# BMS_rev2.net
KiCad netlist of a schematic drawn in Altium Designer
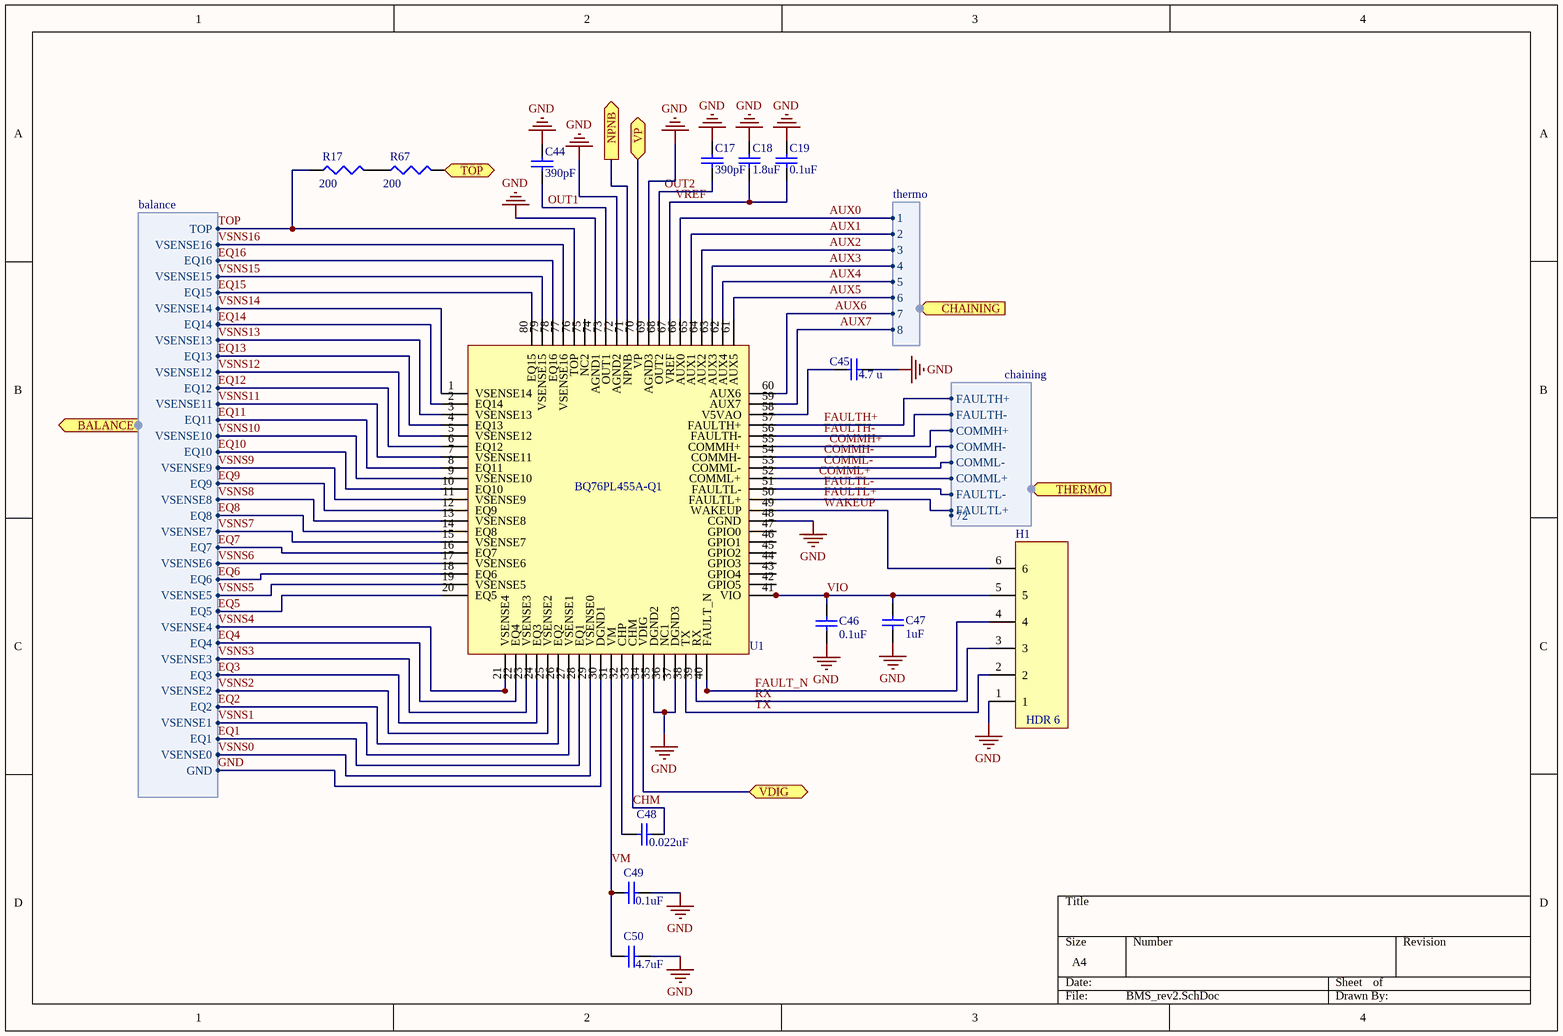
[diagram p0: BMS_rev2.SchDoc]

(export (version "E")
  (design (tool "Eeschema 10.0.6"))
  (components
    (comp (ref "C17")
      (value "390pF")
      (footprint "0805 CAP")
      (description "Capacitor (Semiconductor SIM Model)")
      (fields
        (field (name "MANUFACTURER") "Kyocera AVX")
        (field (name "MANUFACTURER PART NUMBER") "08055A391JAT2A")
        (field (name "PUBLISHER") "Altium Limited")
      )
      (libsource (lib "Miscellaneous Devices") (part "Cap Semi"))
    )
    (comp (ref "C18")
      (value "1.8uF")
      (footprint "1210 cap")
      (description "Capacitor (Semiconductor SIM Model)")
      (fields
        (field (name "MANUFACTURER") "KEMET")
        (field (name "MANUFACTURER PART NUMBER") "C1210C185K3RACTU")
        (field (name "PUBLISHER") "Altium Limited")
      )
      (libsource (lib "Miscellaneous Devices") (part "Cap Semi"))
    )
    (comp (ref "C19")
      (value "0.1uF")
      (footprint "0603 CAP")
      (description "Capacitor (Semiconductor SIM Model)")
      (fields
        (field (name "MANUFACTURER") "KEMET")
        (field (name "MANUFACTURER PART NUMBER") "C0603X104K3RACTU")
        (field (name "PUBLISHER") "Altium Limited")
      )
      (libsource (lib "Miscellaneous Devices") (part "Cap Semi"))
    )
    (comp (ref "C44")
      (value "390pF")
      (footprint "0805 CAP")
      (description "Capacitor (Semiconductor SIM Model)")
      (fields
        (field (name "MANUFACTURER") "Kyocera AVX")
        (field (name "MANUFACTURER PART NUMBER") "08055A391JAT2A")
        (field (name "PUBLISHER") "Altium Limited")
      )
      (libsource (lib "Miscellaneous Devices") (part "Cap Semi"))
    )
    (comp (ref "C45")
      (value "4.7 u")
      (footprint "0805 CAP")
      (description "Capacitor (Semiconductor SIM Model)")
      (fields
        (field (name "MANUFACTURER") "Murata")
        (field (name "MANUFACTURER PART NUMBER") "GRM21BR71C475KA73L")
        (field (name "PUBLISHER") "Altium Limited")
      )
      (libsource (lib "Miscellaneous Devices") (part "Cap Semi"))
    )
    (comp (ref "C46")
      (value "0.1uF")
      (footprint "0603 CAP")
      (description "Capacitor (Semiconductor SIM Model)")
      (fields
        (field (name "MANUFACTURER") "KEMET")
        (field (name "MANUFACTURER PART NUMBER") "C0603X104K3RACTU")
        (field (name "PUBLISHER") "Altium Limited")
      )
      (libsource (lib "Miscellaneous Devices") (part "Cap Semi"))
    )
    (comp (ref "C47")
      (value "1uF")
      (footprint "0603 CAP")
      (description "Capacitor (Semiconductor SIM Model)")
      (fields
        (field (name "MANUFACTURER") "TDK")
        (field (name "MANUFACTURER PART NUMBER") "C1608X7R1C105K080AC")
        (field (name "PUBLISHER") "Altium Limited")
      )
      (libsource (lib "Miscellaneous Devices") (part "Cap Semi"))
    )
    (comp (ref "C48")
      (value "0.022uF")
      (footprint "0603 CAP")
      (description "Capacitor (Semiconductor SIM Model)")
      (fields
        (field (name "MANUFACTURER") "TDK")
        (field (name "MANUFACTURER PART NUMBER") "C1608X7R1H223K080AA")
        (field (name "PUBLISHER") "Altium Limited")
      )
      (libsource (lib "Miscellaneous Devices") (part "Cap Semi"))
    )
    (comp (ref "C49")
      (value "0.1uF")
      (footprint "0603 CAP")
      (description "Capacitor (Semiconductor SIM Model)")
      (fields
        (field (name "MANUFACTURER") "KEMET")
        (field (name "MANUFACTURER PART NUMBER") "C0603X104K3RACTU")
        (field (name "PUBLISHER") "Altium Limited")
      )
      (libsource (lib "Miscellaneous Devices") (part "Cap Semi"))
    )
    (comp (ref "C50")
      (value "4.7uF")
      (footprint "0805 CAP")
      (description "Capacitor (Semiconductor SIM Model)")
      (fields
        (field (name "MANUFACTURER") "Murata")
        (field (name "MANUFACTURER PART NUMBER") "GRM21BR71C475KA73L")
        (field (name "PUBLISHER") "Altium Limited")
      )
      (libsource (lib "Miscellaneous Devices") (part "Cap Semi"))
    )
    (comp (ref "H1")
      (value "HDR 6")
      (footprint "SERIAL HDR")
      (fields (field (name "MANUFACTURER") "Molex") (field (name "MANUFACTURER PART NUMBER") "0022124062"))
      (libsource (lib "parts") (part "HDR 6"))
    )
    (comp (ref "R17")
      (value "200")
      (footprint "2512 RES")
      (description "Resistor")
      (fields
        (field (name "MANUFACTURER") "Vishay Dale")
        (field (name "MANUFACTURER PART NUMBER") "CRCW2512200RJNEG")
        (field (name "PUBLISHER") "Altium Limited")
      )
      (libsource (lib "Miscellaneous Devices") (part "Res3"))
    )
    (comp (ref "R67")
      (value "200")
      (footprint "2512 RES")
      (description "Resistor")
      (fields
        (field (name "MANUFACTURER") "Vishay Dale")
        (field (name "MANUFACTURER PART NUMBER") "CRCW2512200RJNEG")
        (field (name "PUBLISHER") "Altium Limited")
      )
      (libsource (lib "Miscellaneous Devices") (part "Res3"))
    )
    (comp (ref "U1")
      (value "BQ76PL455A-Q1")
      (footprint "BQ76PL455A-Q1")
      (fields
        (field (name "MANUFACTURER") "Texas Instruments")
        (field (name "MANUFACTURER PART NUMBER") "BQ76PL455ATPFCRQ1")
      )
      (libsource (lib "parts") (part "BQ76PL455A-Q1"))
    )
  )
  (nets
    (net (code "4") (name "/AUX0") (class "Default")
      (node (ref "U1") (pin "66") (pinfunction "AUX0_66") (pintype "passive"))
    )
    (net (code "5") (name "/AUX1") (class "Default")
      (node (ref "U1") (pin "65") (pinfunction "AUX1_65") (pintype "passive"))
    )
    (net (code "6") (name "/AUX2") (class "Default")
      (node (ref "U1") (pin "64") (pinfunction "AUX2_64") (pintype "passive"))
    )
    (net (code "7") (name "/AUX3") (class "Default")
      (node (ref "U1") (pin "63") (pinfunction "AUX3_63") (pintype "passive"))
    )
    (net (code "8") (name "/AUX4") (class "Default")
      (node (ref "U1") (pin "62") (pinfunction "AUX4_62") (pintype "passive"))
    )
    (net (code "9") (name "/AUX5") (class "Default")
      (node (ref "U1") (pin "61") (pinfunction "AUX5_61") (pintype "passive"))
    )
    (net (code "10") (name "/AUX6") (class "Default")
      (node (ref "U1") (pin "60") (pinfunction "AUX6_60") (pintype "passive"))
    )
    (net (code "11") (name "/AUX7") (class "Default")
      (node (ref "U1") (pin "59") (pinfunction "AUX7_59") (pintype "passive"))
    )
    (net (code "12") (name "/CHM") (class "Default")
      (node (ref "C48") (pin "2") (pinfunction "2_2") (pintype "passive"))
      (node (ref "U1") (pin "33") (pinfunction "CHM_33") (pintype "passive"))
    )
    (net (code "13") (name "/COMMH+") (class "Default")
      (node (ref "U1") (pin "55") (pinfunction "COMMH+_55") (pintype "passive"))
    )
    (net (code "14") (name "/COMMH-") (class "Default")
      (node (ref "U1") (pin "54") (pinfunction "COMMH-_54") (pintype "passive"))
    )
    (net (code "15") (name "/COMML+") (class "Default")
      (node (ref "U1") (pin "52") (pinfunction "COMML+_52") (pintype "passive"))
    )
    (net (code "16") (name "/COMML-") (class "Default")
      (node (ref "U1") (pin "53") (pinfunction "COMML-_53") (pintype "passive"))
    )
    (net (code "17") (name "/EQ1") (class "Default")
      (node (ref "U1") (pin "28") (pinfunction "EQ1_28") (pintype "passive"))
    )
    (net (code "18") (name "/EQ2") (class "Default")
      (node (ref "U1") (pin "26") (pinfunction "EQ2_26") (pintype "passive"))
    )
    (net (code "19") (name "/EQ3") (class "Default")
      (node (ref "U1") (pin "24") (pinfunction "EQ3_24") (pintype "passive"))
    )
    (net (code "20") (name "/EQ4") (class "Default")
      (node (ref "U1") (pin "22") (pinfunction "EQ4_22") (pintype "passive"))
    )
    (net (code "21") (name "/EQ5") (class "Default")
      (node (ref "U1") (pin "20") (pinfunction "EQ5_20") (pintype "passive"))
    )
    (net (code "22") (name "/EQ6") (class "Default")
      (node (ref "U1") (pin "18") (pinfunction "EQ6_18") (pintype "passive"))
    )
    (net (code "23") (name "/EQ7") (class "Default")
      (node (ref "U1") (pin "16") (pinfunction "EQ7_16") (pintype "passive"))
    )
    (net (code "24") (name "/EQ8") (class "Default")
      (node (ref "U1") (pin "14") (pinfunction "EQ8_14") (pintype "passive"))
    )
    (net (code "25") (name "/EQ9") (class "Default")
      (node (ref "U1") (pin "12") (pinfunction "EQ9_12") (pintype "passive"))
    )
    (net (code "26") (name "/EQ10") (class "Default")
      (node (ref "U1") (pin "10") (pinfunction "EQ10_10") (pintype "passive"))
    )
    (net (code "27") (name "/EQ11") (class "Default")
      (node (ref "U1") (pin "8") (pinfunction "EQ11_8") (pintype "passive"))
    )
    (net (code "28") (name "/EQ12") (class "Default")
      (node (ref "U1") (pin "6") (pinfunction "EQ12_6") (pintype "passive"))
    )
    (net (code "29") (name "/EQ13") (class "Default")
      (node (ref "U1") (pin "4") (pinfunction "EQ13_4") (pintype "passive"))
    )
    (net (code "30") (name "/EQ14") (class "Default")
      (node (ref "U1") (pin "2") (pinfunction "EQ14_2") (pintype "passive"))
    )
    (net (code "31") (name "/EQ15") (class "Default")
      (node (ref "U1") (pin "80") (pinfunction "EQ15_80") (pintype "passive"))
    )
    (net (code "32") (name "/EQ16") (class "Default")
      (node (ref "U1") (pin "78") (pinfunction "EQ16_78") (pintype "passive"))
    )
    (net (code "33") (name "/FAULTH+") (class "Default")
      (node (ref "U1") (pin "57") (pinfunction "FAULTH+_57") (pintype "passive"))
    )
    (net (code "34") (name "/FAULTH-") (class "Default")
      (node (ref "U1") (pin "56") (pinfunction "FAULTH-_56") (pintype "passive"))
    )
    (net (code "35") (name "/FAULTL+") (class "Default")
      (node (ref "U1") (pin "50") (pinfunction "FAULTL+_50") (pintype "passive"))
    )
    (net (code "36") (name "/FAULTL-") (class "Default")
      (node (ref "U1") (pin "51") (pinfunction "FAULTL-_51") (pintype "passive"))
    )
    (net (code "37") (name "/FAULT_N") (class "Default")
      (node (ref "H1") (pin "4") (pinfunction "4_4") (pintype "passive"))
      (node (ref "U1") (pin "40") (pinfunction "FAULT_N_40") (pintype "passive"))
    )
    (net (code "38") (name "/NPNB") (class "Default")
      (node (ref "U1") (pin "71") (pinfunction "NPNB_71") (pintype "passive"))
    )
    (net (code "39") (name "/OUT1") (class "Default")
      (node (ref "C44") (pin "2") (pinfunction "2_2") (pintype "passive"))
      (node (ref "U1") (pin "73") (pinfunction "OUT1_73") (pintype "passive"))
    )
    (net (code "40") (name "/OUT2") (class "Default")
      (node (ref "C17") (pin "2") (pinfunction "2_2") (pintype "passive"))
      (node (ref "U1") (pin "68") (pinfunction "OUT2_68") (pintype "passive"))
    )
    (net (code "41") (name "/RX") (class "Default")
      (node (ref "H1") (pin "3") (pinfunction "3_3") (pintype "passive"))
      (node (ref "U1") (pin "39") (pinfunction "RX_39") (pintype "passive"))
    )
    (net (code "42") (name "/TOP") (class "Default")
      (node (ref "R17") (pin "1") (pinfunction "1_1") (pintype "passive"))
      (node (ref "U1") (pin "76") (pinfunction "TOP_76") (pintype "passive"))
    )
    (net (code "43") (name "/TX") (class "Default")
      (node (ref "H1") (pin "2") (pinfunction "2_2") (pintype "passive"))
      (node (ref "U1") (pin "38") (pinfunction "TX_38") (pintype "passive"))
    )
    (net (code "44") (name "/VDIG") (class "Default")
      (node (ref "U1") (pin "34") (pinfunction "VDIG_34") (pintype "passive"))
    )
    (net (code "45") (name "/VIO") (class "Default")
      (node (ref "C46") (pin "2") (pinfunction "2_2") (pintype "passive"))
      (node (ref "C47") (pin "2") (pinfunction "2_2") (pintype "passive"))
      (node (ref "H1") (pin "5") (pinfunction "5_5") (pintype "passive"))
      (node (ref "U1") (pin "41") (pinfunction "VIO_41") (pintype "passive"))
    )
    (net (code "46") (name "/VM") (class "Default")
      (node (ref "C49") (pin "1") (pinfunction "1_1") (pintype "passive"))
      (node (ref "C50") (pin "1") (pinfunction "1_1") (pintype "passive"))
      (node (ref "U1") (pin "31") (pinfunction "VM_31") (pintype "passive"))
    )
    (net (code "47") (name "/VP") (class "Default")
      (node (ref "U1") (pin "70") (pinfunction "VP_70") (pintype "passive"))
    )
    (net (code "48") (name "/VREF") (class "Default")
      (node (ref "C18") (pin "2") (pinfunction "2_2") (pintype "passive"))
      (node (ref "C19") (pin "2") (pinfunction "2_2") (pintype "passive"))
      (node (ref "U1") (pin "67") (pinfunction "VREF_67") (pintype "passive"))
    )
    (net (code "49") (name "/VSNS0") (class "Default")
      (node (ref "U1") (pin "29") (pinfunction "VSENSE0_29") (pintype "passive"))
    )
    (net (code "50") (name "/VSNS1") (class "Default")
      (node (ref "U1") (pin "27") (pinfunction "VSENSE1_27") (pintype "passive"))
    )
    (net (code "51") (name "/VSNS2") (class "Default")
      (node (ref "U1") (pin "25") (pinfunction "VSENSE2_25") (pintype "passive"))
    )
    (net (code "52") (name "/VSNS3") (class "Default")
      (node (ref "U1") (pin "23") (pinfunction "VSENSE3_23") (pintype "passive"))
    )
    (net (code "53") (name "/VSNS4") (class "Default")
      (node (ref "U1") (pin "21") (pinfunction "VSENSE4_21") (pintype "passive"))
    )
    (net (code "54") (name "/VSNS5") (class "Default")
      (node (ref "U1") (pin "19") (pinfunction "VSENSE5_19") (pintype "passive"))
    )
    (net (code "55") (name "/VSNS6") (class "Default")
      (node (ref "U1") (pin "17") (pinfunction "VSENSE6_17") (pintype "passive"))
    )
    (net (code "56") (name "/VSNS7") (class "Default")
      (node (ref "U1") (pin "15") (pinfunction "VSENSE7_15") (pintype "passive"))
    )
    (net (code "57") (name "/VSNS8") (class "Default")
      (node (ref "U1") (pin "13") (pinfunction "VSENSE8_13") (pintype "passive"))
    )
    (net (code "58") (name "/VSNS9") (class "Default")
      (node (ref "U1") (pin "11") (pinfunction "VSENSE9_11") (pintype "passive"))
    )
    (net (code "59") (name "/VSNS10") (class "Default")
      (node (ref "U1") (pin "9") (pinfunction "VSENSE10_9") (pintype "passive"))
    )
    (net (code "60") (name "/VSNS11") (class "Default")
      (node (ref "U1") (pin "7") (pinfunction "VSENSE11_7") (pintype "passive"))
    )
    (net (code "61") (name "/VSNS12") (class "Default")
      (node (ref "U1") (pin "5") (pinfunction "VSENSE12_5") (pintype "passive"))
    )
    (net (code "62") (name "/VSNS13") (class "Default")
      (node (ref "U1") (pin "3") (pinfunction "VSENSE13_3") (pintype "passive"))
    )
    (net (code "63") (name "/VSNS14") (class "Default")
      (node (ref "U1") (pin "1") (pinfunction "VSENSE14_1") (pintype "passive"))
    )
    (net (code "64") (name "/VSNS15") (class "Default")
      (node (ref "U1") (pin "79") (pinfunction "VSENSE15_79") (pintype "passive"))
    )
    (net (code "65") (name "/VSNS16") (class "Default")
      (node (ref "U1") (pin "77") (pinfunction "VSENSE16_77") (pintype "passive"))
    )
    (net (code "66") (name "/WAKEUP") (class "Default")
      (node (ref "H1") (pin "6") (pinfunction "6_6") (pintype "passive"))
      (node (ref "U1") (pin "49") (pinfunction "WAKEUP_49") (pintype "passive"))
    )
    (net (code "70") (name "GND") (class "Default")
      (node (ref "C17") (pin "1") (pinfunction "1_1") (pintype "passive"))
      (node (ref "C18") (pin "1") (pinfunction "1_1") (pintype "passive"))
      (node (ref "C19") (pin "1") (pinfunction "1_1") (pintype "passive"))
      (node (ref "C44") (pin "1") (pinfunction "1_1") (pintype "passive"))
      (node (ref "C45") (pin "2") (pinfunction "2_2") (pintype "passive"))
      (node (ref "C46") (pin "1") (pinfunction "1_1") (pintype "passive"))
      (node (ref "C47") (pin "1") (pinfunction "1_1") (pintype "passive"))
      (node (ref "C49") (pin "2") (pinfunction "2_2") (pintype "passive"))
      (node (ref "C50") (pin "2") (pinfunction "2_2") (pintype "passive"))
      (node (ref "H1") (pin "1") (pinfunction "1_1") (pintype "passive"))
      (node (ref "U1") (pin "30") (pinfunction "DGND1_30") (pintype "passive"))
      (node (ref "U1") (pin "35") (pinfunction "DGND2_35") (pintype "passive"))
      (node (ref "U1") (pin "37") (pinfunction "DGND3_37") (pintype "passive"))
      (node (ref "U1") (pin "48") (pinfunction "CGND_48") (pintype "passive"))
      (node (ref "U1") (pin "69") (pinfunction "AGND3_69") (pintype "passive"))
      (node (ref "U1") (pin "72") (pinfunction "AGND2_72") (pintype "passive"))
      (node (ref "U1") (pin "74") (pinfunction "AGND1_74") (pintype "passive"))
    )
    (net (code "71") (name "Net-(R17-Pad2)") (class "Default")
      (node (ref "R17") (pin "2") (pinfunction "2_2") (pintype "passive"))
      (node (ref "R67") (pin "1") (pinfunction "1_1") (pintype "passive"))
    )
    (net (code "72") (name "Net-(U1-CHP)") (class "Default")
      (node (ref "C48") (pin "1") (pinfunction "1_1") (pintype "passive"))
      (node (ref "U1") (pin "32") (pinfunction "CHP_32") (pintype "passive"))
    )
    (net (code "73") (name "Net-(U1-V5VAO)") (class "Default")
      (node (ref "C45") (pin "1") (pinfunction "1_1") (pintype "passive"))
      (node (ref "U1") (pin "58") (pinfunction "V5VAO_58") (pintype "passive"))
    )
    (net (code "74") (name "unconnected-(R67-Pad2)") (class "Default")
      (node (ref "R67") (pin "2") (pinfunction "2_2") (pintype "passive"))
    )
    (net (code "75") (name "unconnected-(U1-GPIO0-Pad47)") (class "Default")
      (node (ref "U1") (pin "47") (pinfunction "GPIO0_47") (pintype "passive"))
    )
    (net (code "76") (name "unconnected-(U1-GPIO1-Pad46)") (class "Default")
      (node (ref "U1") (pin "46") (pinfunction "GPIO1_46") (pintype "passive"))
    )
    (net (code "77") (name "unconnected-(U1-GPIO2-Pad45)") (class "Default")
      (node (ref "U1") (pin "45") (pinfunction "GPIO2_45") (pintype "passive"))
    )
    (net (code "78") (name "unconnected-(U1-GPIO3-Pad44)") (class "Default")
      (node (ref "U1") (pin "44") (pinfunction "GPIO3_44") (pintype "passive"))
    )
    (net (code "79") (name "unconnected-(U1-GPIO4-Pad43)") (class "Default")
      (node (ref "U1") (pin "43") (pinfunction "GPIO4_43") (pintype "passive"))
    )
    (net (code "80") (name "unconnected-(U1-GPIO5-Pad42)") (class "Default")
      (node (ref "U1") (pin "42") (pinfunction "GPIO5_42") (pintype "passive"))
    )
    (net (code "81") (name "unconnected-(U1-NC1-Pad36)") (class "Default")
      (node (ref "U1") (pin "36") (pinfunction "NC1_36") (pintype "passive"))
    )
    (net (code "82") (name "unconnected-(U1-NC2-Pad75)") (class "Default")
      (node (ref "U1") (pin "75") (pinfunction "NC2_75") (pintype "passive"))
    )
  )
)
